# caram2-mrf-spi-r1.net
KiCad netlist of a schematic drawn in EAGLE
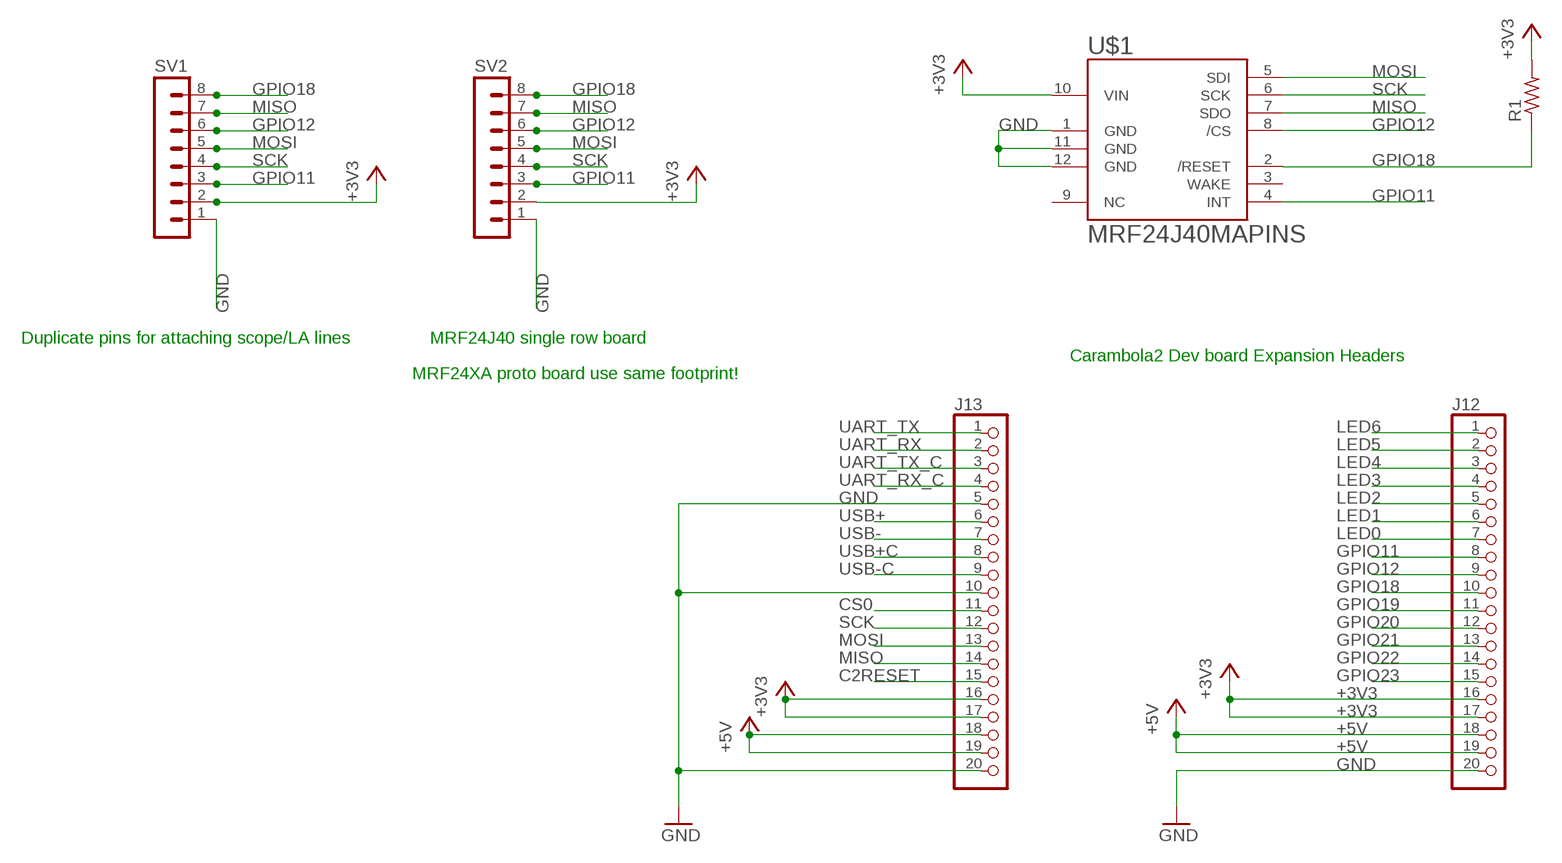
[diagram p0: schematic, sheet 1]

(export (version "E")
  (design (tool "Eeschema 10.0.6"))
  (components
    (comp (ref "J12")
      (value "PINHD-1X20")
      (footprint "eagle-import:1X20")
      (libsource (lib "eagle-import") (part "PINHD-1X20"))
    )
    (comp (ref "J13")
      (value "PINHD-1X20")
      (footprint "eagle-import:1X20")
      (libsource (lib "eagle-import") (part "PINHD-1X20"))
    )
    (comp (ref "R1")
      (value "R-US_R0805")
      (footprint "eagle-import:R0805")
      (libsource (lib "eagle-import") (part "R-US_R0805"))
    )
    (comp (ref "SV1")
      (value "MA08-1")
      (footprint "eagle-import:MA08-1")
      (libsource (lib "eagle-import") (part "MA08-1"))
    )
    (comp (ref "SV2")
      (value "MA08-1")
      (footprint "eagle-import:MA08-1")
      (libsource (lib "eagle-import") (part "MA08-1"))
    )
    (comp (ref "U$1")
      (value "MRF24J40MAPINS")
      (footprint "eagle-import:MRF24J40MA")
      (libsource (lib "eagle-import") (part "MRF24J40MAPINS"))
    )
  )
  (nets
    (net (code "1") (name "+3V3") (class "Default")
      (node (ref "J12") (pin "16") (pinfunction "16_16") (pintype "passive"))
      (node (ref "J12") (pin "17") (pinfunction "17_17") (pintype "passive"))
      (node (ref "J13") (pin "16") (pinfunction "16_16") (pintype "passive"))
      (node (ref "J13") (pin "17") (pinfunction "17_17") (pintype "passive"))
      (node (ref "R1") (pin "2") (pinfunction "2_2") (pintype "passive"))
      (node (ref "SV1") (pin "2") (pinfunction "2_2") (pintype "passive"))
      (node (ref "SV2") (pin "2") (pinfunction "2_2") (pintype "passive"))
      (node (ref "U$1") (pin "10") (pinfunction "VIN_10") (pintype "power_in"))
    )
    (net (code "2") (name "+5V") (class "Default")
      (node (ref "J12") (pin "18") (pinfunction "18_18") (pintype "passive"))
      (node (ref "J12") (pin "19") (pinfunction "19_19") (pintype "passive"))
      (node (ref "J13") (pin "18") (pinfunction "18_18") (pintype "passive"))
      (node (ref "J13") (pin "19") (pinfunction "19_19") (pintype "passive"))
    )
    (net (code "3") (name "/C2RESET") (class "Default")
      (node (ref "J13") (pin "15") (pinfunction "15_15") (pintype "passive"))
    )
    (net (code "4") (name "/CS0") (class "Default")
      (node (ref "J13") (pin "11") (pinfunction "11_11") (pintype "passive"))
    )
    (net (code "5") (name "/GPIO11") (class "Default")
      (node (ref "J12") (pin "8") (pinfunction "8_8") (pintype "passive"))
      (node (ref "SV1") (pin "3") (pinfunction "3_3") (pintype "passive"))
      (node (ref "SV2") (pin "3") (pinfunction "3_3") (pintype "passive"))
      (node (ref "U$1") (pin "4") (pinfunction "INT_4") (pintype "bidirectional"))
    )
    (net (code "6") (name "/GPIO12") (class "Default")
      (node (ref "J12") (pin "9") (pinfunction "9_9") (pintype "passive"))
      (node (ref "SV1") (pin "6") (pinfunction "6_6") (pintype "passive"))
      (node (ref "SV2") (pin "6") (pinfunction "6_6") (pintype "passive"))
      (node (ref "U$1") (pin "8") (pinfunction "/CS_8") (pintype "input"))
    )
    (net (code "7") (name "/GPIO18") (class "Default")
      (node (ref "J12") (pin "10") (pinfunction "10_10") (pintype "passive"))
      (node (ref "R1") (pin "1") (pinfunction "1_1") (pintype "passive"))
      (node (ref "SV1") (pin "8") (pinfunction "8_8") (pintype "passive"))
      (node (ref "SV2") (pin "8") (pinfunction "8_8") (pintype "passive"))
      (node (ref "U$1") (pin "2") (pinfunction "/RESET_2") (pintype "input"))
    )
    (net (code "8") (name "/GPIO19") (class "Default")
      (node (ref "J12") (pin "11") (pinfunction "11_11") (pintype "passive"))
    )
    (net (code "9") (name "/GPIO20") (class "Default")
      (node (ref "J12") (pin "12") (pinfunction "12_12") (pintype "passive"))
    )
    (net (code "10") (name "/GPIO21") (class "Default")
      (node (ref "J12") (pin "13") (pinfunction "13_13") (pintype "passive"))
    )
    (net (code "11") (name "/GPIO22") (class "Default")
      (node (ref "J12") (pin "14") (pinfunction "14_14") (pintype "passive"))
    )
    (net (code "12") (name "/GPIO23") (class "Default")
      (node (ref "J12") (pin "15") (pinfunction "15_15") (pintype "passive"))
    )
    (net (code "13") (name "/LED0") (class "Default")
      (node (ref "J12") (pin "7") (pinfunction "7_7") (pintype "passive"))
    )
    (net (code "14") (name "/LED1") (class "Default")
      (node (ref "J12") (pin "6") (pinfunction "6_6") (pintype "passive"))
    )
    (net (code "15") (name "/LED2") (class "Default")
      (node (ref "J12") (pin "5") (pinfunction "5_5") (pintype "passive"))
    )
    (net (code "16") (name "/LED3") (class "Default")
      (node (ref "J12") (pin "4") (pinfunction "4_4") (pintype "passive"))
    )
    (net (code "17") (name "/LED4") (class "Default")
      (node (ref "J12") (pin "3") (pinfunction "3_3") (pintype "passive"))
    )
    (net (code "18") (name "/LED5") (class "Default")
      (node (ref "J12") (pin "2") (pinfunction "2_2") (pintype "passive"))
    )
    (net (code "19") (name "/LED6") (class "Default")
      (node (ref "J12") (pin "1") (pinfunction "1_1") (pintype "passive"))
    )
    (net (code "20") (name "/MISO") (class "Default")
      (node (ref "J13") (pin "14") (pinfunction "14_14") (pintype "passive"))
      (node (ref "SV1") (pin "7") (pinfunction "7_7") (pintype "passive"))
      (node (ref "SV2") (pin "7") (pinfunction "7_7") (pintype "passive"))
      (node (ref "U$1") (pin "7") (pinfunction "SDO_7") (pintype "output"))
    )
    (net (code "21") (name "/MOSI") (class "Default")
      (node (ref "J13") (pin "13") (pinfunction "13_13") (pintype "passive"))
      (node (ref "SV1") (pin "5") (pinfunction "5_5") (pintype "passive"))
      (node (ref "SV2") (pin "5") (pinfunction "5_5") (pintype "passive"))
      (node (ref "U$1") (pin "5") (pinfunction "SDI_5") (pintype "input"))
    )
    (net (code "22") (name "/SCK") (class "Default")
      (node (ref "J13") (pin "12") (pinfunction "12_12") (pintype "passive"))
      (node (ref "SV1") (pin "4") (pinfunction "4_4") (pintype "passive"))
      (node (ref "SV2") (pin "4") (pinfunction "4_4") (pintype "passive"))
      (node (ref "U$1") (pin "6") (pinfunction "SCK_6") (pintype "bidirectional"))
    )
    (net (code "23") (name "/UART_RX") (class "Default")
      (node (ref "J13") (pin "2") (pinfunction "2_2") (pintype "passive"))
    )
    (net (code "24") (name "/UART_RX_C") (class "Default")
      (node (ref "J13") (pin "4") (pinfunction "4_4") (pintype "passive"))
    )
    (net (code "25") (name "/UART_TX") (class "Default")
      (node (ref "J13") (pin "1") (pinfunction "1_1") (pintype "passive"))
    )
    (net (code "26") (name "/UART_TX_C") (class "Default")
      (node (ref "J13") (pin "3") (pinfunction "3_3") (pintype "passive"))
    )
    (net (code "27") (name "/USB+") (class "Default")
      (node (ref "J13") (pin "6") (pinfunction "6_6") (pintype "passive"))
    )
    (net (code "28") (name "/USB+C") (class "Default")
      (node (ref "J13") (pin "8") (pinfunction "8_8") (pintype "passive"))
    )
    (net (code "29") (name "/USB-") (class "Default")
      (node (ref "J13") (pin "7") (pinfunction "7_7") (pintype "passive"))
    )
    (net (code "30") (name "/USB-C") (class "Default")
      (node (ref "J13") (pin "9") (pinfunction "9_9") (pintype "passive"))
    )
    (net (code "31") (name "GND") (class "Default")
      (node (ref "J12") (pin "20") (pinfunction "20_20") (pintype "passive"))
      (node (ref "J13") (pin "10") (pinfunction "10_10") (pintype "passive"))
      (node (ref "J13") (pin "20") (pinfunction "20_20") (pintype "passive"))
      (node (ref "J13") (pin "5") (pinfunction "5_5") (pintype "passive"))
      (node (ref "SV1") (pin "1") (pinfunction "1_1") (pintype "passive"))
      (node (ref "SV2") (pin "1") (pinfunction "1_1") (pintype "passive"))
      (node (ref "U$1") (pin "1") (pinfunction "GND_1") (pintype "power_in"))
      (node (ref "U$1") (pin "11") (pinfunction "GND_11") (pintype "power_in"))
      (node (ref "U$1") (pin "12") (pinfunction "GND_12") (pintype "power_in"))
    )
    (net (code "32") (name "unconnected-(U$1-NC-Pad9)") (class "Default")
      (node (ref "U$1") (pin "9") (pinfunction "NC_9") (pintype "no_connect"))
    )
    (net (code "33") (name "unconnected-(U$1-WAKE-Pad3)") (class "Default")
      (node (ref "U$1") (pin "3") (pinfunction "WAKE_3") (pintype "bidirectional"))
    )
  )
)
